# Switch.net
KiCad netlist of a schematic drawn in Altium Designer
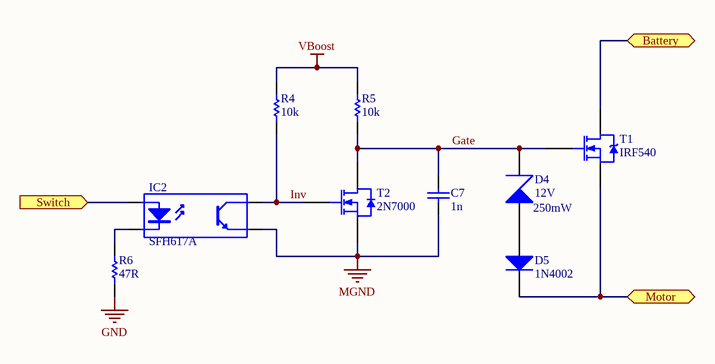
[diagram p0: Switch.SchDoc]

(export (version "E")
  (design (tool "Eeschema 10.0.6"))
  (components
    (comp (ref "C7")
      (value "1n")
      (footprint "CAP-0.4-FILM")
      (description "Capacitor")
      (fields (field (name "PUBLISHER") "Altium Limited"))
      (libsource (lib "Miscellaneous Devices") (part "Cap"))
    )
    (comp (ref "D4")
      (value "12V")
      (footprint "DIODE-0.3-ZENER")
      (description "Zener Diode")
      (fields (field (name "POWER") "250mW") (field (name "PUBLISHER") "Altium Limited"))
      (libsource (lib "std") (part "Diode Zener"))
    )
    (comp (ref "D5")
      (value "1N4002")
      (footprint "DIODE-0.3-SI")
      (description "1 Amp General Purpose Rectifier")
      (fields (field (name "PUBLISHER") "Altium Limited"))
      (libsource (lib "Miscellaneous Devices") (part "Diode 1N4002"))
    )
    (comp (ref "IC2")
      (value "SFH617A")
      (footprint "IC-DIP-4")
      (description "4-Pin Phototransistor Optocoupler")
      (fields (field (name "PUBLISHER") "Altium Limited"))
      (libsource (lib "Miscellaneous Devices") (part "Optoisolator1"))
    )
    (comp (ref "R4")
      (value "10k")
      (footprint "RES-0.6")
      (description "Resistor")
      (fields (field (name "PUBLISHER") "Altium Limited"))
      (libsource (lib "Miscellaneous Devices") (part "Res1"))
    )
    (comp (ref "R5")
      (value "10k")
      (footprint "RES-0.6")
      (description "Resistor")
      (fields (field (name "PUBLISHER") "Altium Limited"))
      (libsource (lib "Miscellaneous Devices") (part "Res1"))
    )
    (comp (ref "R6")
      (value "47R")
      (footprint "RES-0.4")
      (description "Resistor")
      (fields (field (name "PUBLISHER") "Altium Limited"))
      (libsource (lib "Miscellaneous Devices") (part "Res1"))
    )
    (comp (ref "T1")
      (value "IRF540")
      (footprint "TO-220H")
      (description "HEXFET N-Channel Power MOSFET")
      (fields (field (name "PUBLISHER") "Altium Limited"))
      (libsource (lib "IR Discrete MOSFET - Power") (part "IRF540"))
    )
    (comp (ref "T2")
      (value "2N7000")
      (footprint "TO-92-T")
      (description "N-channel Enhancement Mode Field-effect Transistor")
      (fields (field (name "PUBLISHER") "Altium Limited"))
      (libsource (lib "Philips Discrete MOSFET - Low Power") (part "2N7000"))
    )
  )
  (nets
    (net (code "1") (name "/Battery") (class "Default")
      (node (ref "T1") (pin "2") (pinfunction "D_2") (pintype "passive"))
    )
    (net (code "2") (name "/Gate") (class "Default")
      (node (ref "C7") (pin "2") (pinfunction "2_2") (pintype "passive"))
      (node (ref "D4") (pin "2") (pinfunction "K_2") (pintype "passive"))
      (node (ref "R5") (pin "2") (pinfunction "2_2") (pintype "passive"))
      (node (ref "T1") (pin "1") (pinfunction "G_1") (pintype "passive"))
      (node (ref "T2") (pin "1") (pinfunction "D_1") (pintype "passive"))
    )
    (net (code "3") (name "/Inv") (class "Default")
      (node (ref "IC2") (pin "4") (pinfunction "C_4") (pintype "passive"))
      (node (ref "R4") (pin "2") (pinfunction "2_2") (pintype "passive"))
      (node (ref "T2") (pin "2") (pinfunction "G_2") (pintype "passive"))
    )
    (net (code "4") (name "/Motor") (class "Default")
      (node (ref "D5") (pin "2") (pinfunction "K_2") (pintype "passive"))
      (node (ref "T1") (pin "3") (pinfunction "S_3") (pintype "passive"))
    )
    (net (code "5") (name "/Switch") (class "Default")
      (node (ref "IC2") (pin "1") (pinfunction "A_1") (pintype "passive"))
    )
    (net (code "6") (name "GND") (class "Default")
      (node (ref "R6") (pin "2") (pinfunction "2_2") (pintype "passive"))
    )
    (net (code "7") (name "MGND") (class "Default")
      (node (ref "C7") (pin "1") (pinfunction "1_1") (pintype "passive"))
      (node (ref "IC2") (pin "3") (pinfunction "E_3") (pintype "passive"))
      (node (ref "T2") (pin "3") (pinfunction "S_3") (pintype "passive"))
    )
    (net (code "8") (name "Net-(D4-A)") (class "Default")
      (node (ref "D4") (pin "1") (pinfunction "A_1") (pintype "passive"))
      (node (ref "D5") (pin "1") (pinfunction "A_1") (pintype "passive"))
    )
    (net (code "9") (name "Net-(IC2-K)") (class "Default")
      (node (ref "IC2") (pin "2") (pinfunction "K_2") (pintype "passive"))
      (node (ref "R6") (pin "1") (pinfunction "1_1") (pintype "passive"))
    )
    (net (code "10") (name "VBoost") (class "Default")
      (node (ref "R4") (pin "1") (pinfunction "1_1") (pintype "passive"))
      (node (ref "R5") (pin "1") (pinfunction "1_1") (pintype "passive"))
    )
  )
)
